# ROM.net
KiCad netlist of a schematic drawn in Altium Designer
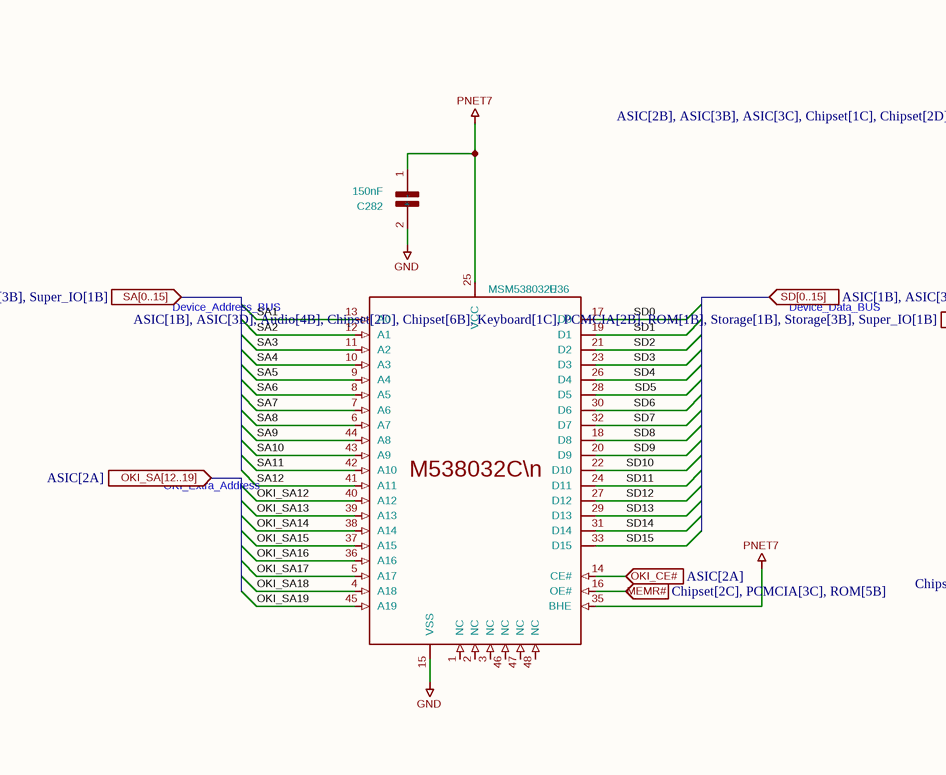
[diagram p0: ROM.SchDoc, left]
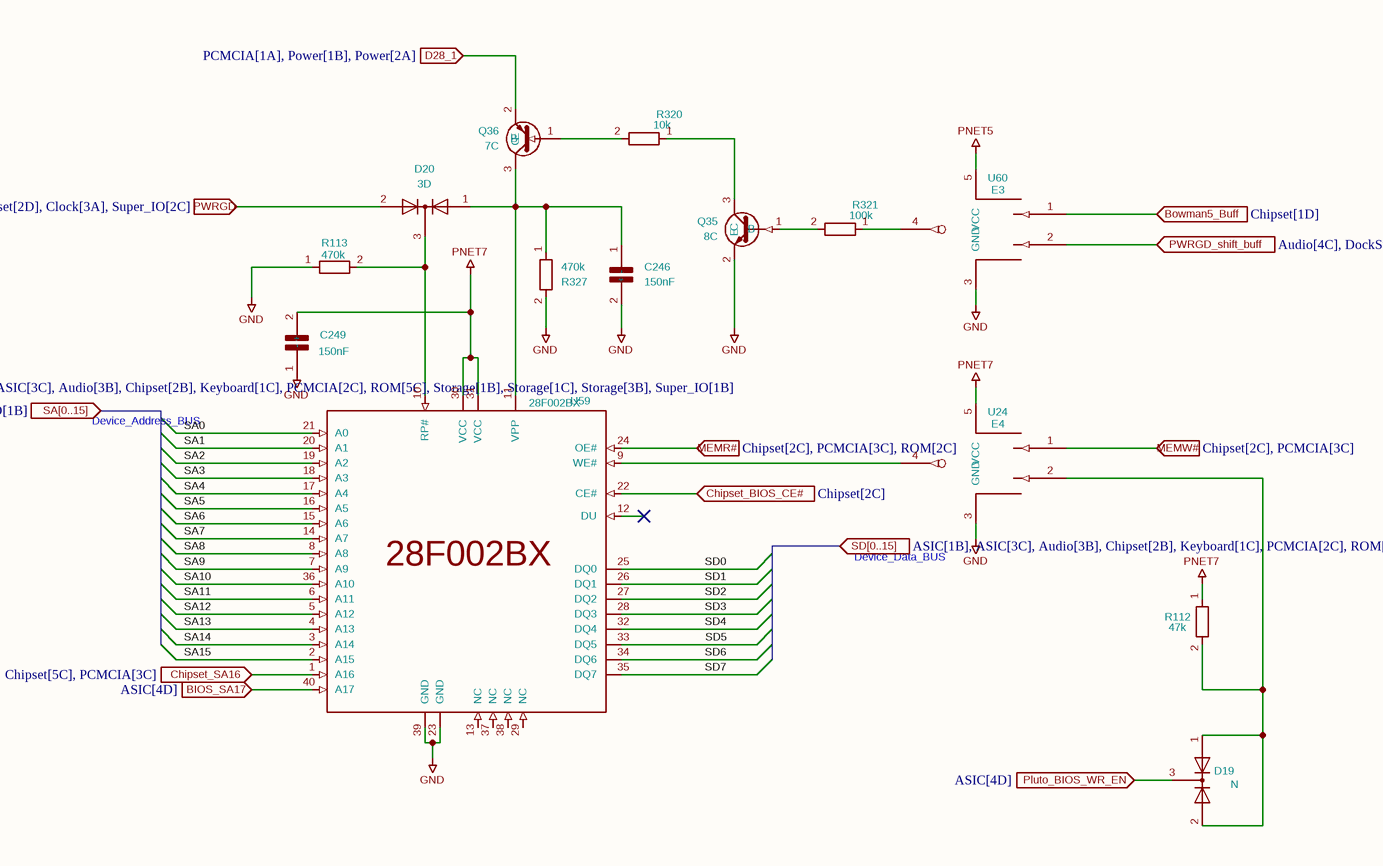
[diagram p1: ROM.SchDoc, right]

(export (version "E")
  (design (tool "Eeschema 10.0.6"))
  (components
    (comp (ref "C246") (value "150nF") (footprint "C_0603_1608Metric") (libsource (lib "") (part "C_1")))
    (comp (ref "C249")
      (value "150nF")
      (footprint "C_0402_1005Metric")
      (libsource (lib "PCM_Elektuur") (part "C"))
    )
    (comp (ref "C282") (value "150nF") (footprint "C_0402_1005Metric") (libsource (lib "") (part "C_1")))
    (comp (ref "D19") (value "N") (footprint "SOT-416L") (libsource (lib "PC110") (part "3D_Diode")))
    (comp (ref "D20") (value "3D") (footprint "SOT-416L") (libsource (lib "PC110") (part "3D_Diode")))
    (comp (ref "Q35") (value "8C") (footprint "SOT-523") (libsource (lib "Transistor_BJT") (part "MMBTA44")))
    (comp (ref "Q36")
      (value "7C")
      (footprint "TSOT-23")
      (libsource (lib "PCM_Transistor_BJT_AKL") (part "Q_PNP_Generic_BEC"))
    )
    (comp (ref "R112") (value "47k") (footprint "R_0402_1005Metric") (libsource (lib "") (part "R_1")))
    (comp (ref "R113") (value "470k") (footprint "R_0402_1005Metric") (libsource (lib "") (part "R_2")))
    (comp (ref "R320") (value "10k") (footprint "R_0402_1005Metric") (libsource (lib "Device") (part "R")))
    (comp (ref "R321") (value "100k") (footprint "R_0402_1005Metric") (libsource (lib "Device") (part "R")))
    (comp (ref "R327") (value "470k") (footprint "R_0402_1005Metric") (libsource (lib "Device") (part "R")))
    (comp (ref "U24") (value "E4") (footprint "SOT-353") (libsource (lib "74xGxx") (part "74AUP1G02")))
    (comp (ref "U36") (value "MSM538032E") (footprint "SOP48") (libsource (lib "PC110") (part "M538032C")))
    (comp (ref "U59") (value "28F002BX") (footprint "Flash-40") (libsource (lib "PC110") (part "28F002BX")))
    (comp (ref "U60") (value "E3") (footprint "SOT-353") (libsource (lib "74xGxx") (part "74AUP1G02")))
  )
  (nets
    (net (code "1") (name "/BIOS_SA17") (class "Default")
      (node (ref "U59") (pin "40") (pinfunction "A17_40") (pintype "input"))
    )
    (net (code "2") (name "/Bowman5_Buff") (class "Default")
      (node (ref "U60") (pin "1") (pinfunction "1_1") (pintype "input"))
    )
    (net (code "3") (name "/Chipset_BIOS_CE#") (class "Default")
      (node (ref "U59") (pin "22") (pinfunction "CE#_22") (pintype "input"))
    )
    (net (code "4") (name "/Chipset_SA16") (class "Default")
      (node (ref "U59") (pin "1") (pinfunction "A16_1") (pintype "input"))
    )
    (net (code "5") (name "/D28_1") (class "Default")
      (node (ref "Q36") (pin "2") (pinfunction "E_2") (pintype "passive"))
    )
    (net (code "6") (name "/MEMR#") (class "Default")
      (node (ref "U36") (pin "16") (pinfunction "OE#_16") (pintype "input"))
      (node (ref "U59") (pin "24") (pinfunction "OE#_24") (pintype "input"))
    )
    (net (code "7") (name "/MEMW#") (class "Default")
      (node (ref "U24") (pin "1") (pinfunction "1_1") (pintype "input"))
    )
    (net (code "8") (name "/OKI_CE#") (class "Default")
      (node (ref "U36") (pin "14") (pinfunction "CE#_14") (pintype "input"))
    )
    (net (code "9") (name "/OKI_SA12") (class "Default")
      (node (ref "U36") (pin "40") (pinfunction "A12_40") (pintype "input"))
    )
    (net (code "10") (name "/OKI_SA13") (class "Default")
      (node (ref "U36") (pin "39") (pinfunction "A13_39") (pintype "input"))
    )
    (net (code "11") (name "/OKI_SA14") (class "Default")
      (node (ref "U36") (pin "38") (pinfunction "A14_38") (pintype "input"))
    )
    (net (code "12") (name "/OKI_SA15") (class "Default")
      (node (ref "U36") (pin "37") (pinfunction "A15_37") (pintype "input"))
    )
    (net (code "13") (name "/OKI_SA16") (class "Default")
      (node (ref "U36") (pin "36") (pinfunction "A16_36") (pintype "input"))
    )
    (net (code "14") (name "/OKI_SA17") (class "Default")
      (node (ref "U36") (pin "5") (pinfunction "A17_5") (pintype "input"))
    )
    (net (code "15") (name "/OKI_SA18") (class "Default")
      (node (ref "U36") (pin "4") (pinfunction "A18_4") (pintype "input"))
    )
    (net (code "16") (name "/OKI_SA19") (class "Default")
      (node (ref "U36") (pin "45") (pinfunction "A19_45") (pintype "input"))
    )
    (net (code "18") (name "/PWRGD") (class "Default")
      (node (ref "D20") (pin "2") (pinfunction "2_2") (pintype "passive"))
    )
    (net (code "19") (name "/PWRGD_shift_buff") (class "Default")
      (node (ref "U60") (pin "2") (pinfunction "2_2") (pintype "input"))
    )
    (net (code "20") (name "/Pluto_BIOS_WR_EN") (class "Default")
      (node (ref "D19") (pin "3") (pinfunction "3_3") (pintype "passive"))
    )
    (net (code "21") (name "/SA0") (class "Default")
      (node (ref "U59") (pin "21") (pinfunction "A0_21") (pintype "input"))
    )
    (net (code "22") (name "/SA1") (class "Default")
      (node (ref "U36") (pin "13") (pinfunction "A0_13") (pintype "input"))
      (node (ref "U59") (pin "20") (pinfunction "A1_20") (pintype "input"))
    )
    (net (code "23") (name "/SA2") (class "Default")
      (node (ref "U36") (pin "12") (pinfunction "A1_12") (pintype "input"))
      (node (ref "U59") (pin "19") (pinfunction "A2_19") (pintype "input"))
    )
    (net (code "24") (name "/SA3") (class "Default")
      (node (ref "U36") (pin "11") (pinfunction "A2_11") (pintype "input"))
      (node (ref "U59") (pin "18") (pinfunction "A3_18") (pintype "input"))
    )
    (net (code "25") (name "/SA4") (class "Default")
      (node (ref "U36") (pin "10") (pinfunction "A3_10") (pintype "input"))
      (node (ref "U59") (pin "17") (pinfunction "A4_17") (pintype "input"))
    )
    (net (code "26") (name "/SA5") (class "Default")
      (node (ref "U36") (pin "9") (pinfunction "A4_9") (pintype "input"))
      (node (ref "U59") (pin "16") (pinfunction "A5_16") (pintype "input"))
    )
    (net (code "27") (name "/SA6") (class "Default")
      (node (ref "U36") (pin "8") (pinfunction "A5_8") (pintype "input"))
      (node (ref "U59") (pin "15") (pinfunction "A6_15") (pintype "input"))
    )
    (net (code "28") (name "/SA7") (class "Default")
      (node (ref "U36") (pin "7") (pinfunction "A6_7") (pintype "input"))
      (node (ref "U59") (pin "14") (pinfunction "A7_14") (pintype "input"))
    )
    (net (code "29") (name "/SA8") (class "Default")
      (node (ref "U36") (pin "6") (pinfunction "A7_6") (pintype "input"))
      (node (ref "U59") (pin "8") (pinfunction "A8_8") (pintype "input"))
    )
    (net (code "30") (name "/SA9") (class "Default")
      (node (ref "U36") (pin "44") (pinfunction "A8_44") (pintype "input"))
      (node (ref "U59") (pin "7") (pinfunction "A9_7") (pintype "input"))
    )
    (net (code "31") (name "/SA10") (class "Default")
      (node (ref "U36") (pin "43") (pinfunction "A9_43") (pintype "input"))
      (node (ref "U59") (pin "36") (pinfunction "A10_36") (pintype "input"))
    )
    (net (code "32") (name "/SA11") (class "Default")
      (node (ref "U36") (pin "42") (pinfunction "A10_42") (pintype "input"))
      (node (ref "U59") (pin "6") (pinfunction "A11_6") (pintype "input"))
    )
    (net (code "33") (name "/SA12") (class "Default")
      (node (ref "U36") (pin "41") (pinfunction "A11_41") (pintype "input"))
      (node (ref "U59") (pin "5") (pinfunction "A12_5") (pintype "input"))
    )
    (net (code "34") (name "/SA13") (class "Default")
      (node (ref "U59") (pin "4") (pinfunction "A13_4") (pintype "input"))
    )
    (net (code "35") (name "/SA14") (class "Default")
      (node (ref "U59") (pin "3") (pinfunction "A14_3") (pintype "input"))
    )
    (net (code "36") (name "/SA15") (class "Default")
      (node (ref "U59") (pin "2") (pinfunction "A15_2") (pintype "input"))
    )
    (net (code "38") (name "/SD0") (class "Default")
      (node (ref "U36") (pin "17") (pinfunction "D0_17") (pintype "bidirectional"))
      (node (ref "U59") (pin "25") (pinfunction "DQ0_25") (pintype "bidirectional"))
    )
    (net (code "39") (name "/SD1") (class "Default")
      (node (ref "U36") (pin "19") (pinfunction "D1_19") (pintype "bidirectional"))
      (node (ref "U59") (pin "26") (pinfunction "DQ1_26") (pintype "bidirectional"))
    )
    (net (code "40") (name "/SD2") (class "Default")
      (node (ref "U36") (pin "21") (pinfunction "D2_21") (pintype "bidirectional"))
      (node (ref "U59") (pin "27") (pinfunction "DQ2_27") (pintype "bidirectional"))
    )
    (net (code "41") (name "/SD3") (class "Default")
      (node (ref "U36") (pin "23") (pinfunction "D3_23") (pintype "bidirectional"))
      (node (ref "U59") (pin "28") (pinfunction "DQ3_28") (pintype "bidirectional"))
    )
    (net (code "42") (name "/SD4") (class "Default")
      (node (ref "U36") (pin "26") (pinfunction "D4_26") (pintype "bidirectional"))
      (node (ref "U59") (pin "32") (pinfunction "DQ4_32") (pintype "bidirectional"))
    )
    (net (code "43") (name "/SD5") (class "Default")
      (node (ref "U36") (pin "28") (pinfunction "D5_28") (pintype "bidirectional"))
      (node (ref "U59") (pin "33") (pinfunction "DQ5_33") (pintype "bidirectional"))
    )
    (net (code "44") (name "/SD6") (class "Default")
      (node (ref "U36") (pin "30") (pinfunction "D6_30") (pintype "bidirectional"))
      (node (ref "U59") (pin "34") (pinfunction "DQ6_34") (pintype "bidirectional"))
    )
    (net (code "45") (name "/SD7") (class "Default")
      (node (ref "U36") (pin "32") (pinfunction "D7_32") (pintype "bidirectional"))
      (node (ref "U59") (pin "35") (pinfunction "DQ7_35") (pintype "bidirectional"))
    )
    (net (code "46") (name "/SD8") (class "Default")
      (node (ref "U36") (pin "18") (pinfunction "D8_18") (pintype "bidirectional"))
    )
    (net (code "47") (name "/SD9") (class "Default")
      (node (ref "U36") (pin "20") (pinfunction "D9_20") (pintype "bidirectional"))
    )
    (net (code "48") (name "/SD10") (class "Default")
      (node (ref "U36") (pin "22") (pinfunction "D10_22") (pintype "bidirectional"))
    )
    (net (code "49") (name "/SD11") (class "Default")
      (node (ref "U36") (pin "24") (pinfunction "D11_24") (pintype "bidirectional"))
    )
    (net (code "50") (name "/SD12") (class "Default")
      (node (ref "U36") (pin "27") (pinfunction "D12_27") (pintype "bidirectional"))
    )
    (net (code "51") (name "/SD13") (class "Default")
      (node (ref "U36") (pin "29") (pinfunction "D13_29") (pintype "bidirectional"))
    )
    (net (code "52") (name "/SD14") (class "Default")
      (node (ref "U36") (pin "31") (pinfunction "D14_31") (pintype "bidirectional"))
    )
    (net (code "53") (name "/SD15") (class "Default")
      (node (ref "U36") (pin "33") (pinfunction "D15_33") (pintype "bidirectional"))
    )
    (net (code "55") (name "GND") (class "Default")
      (node (ref "C246") (pin "2") (pinfunction "-_2") (pintype "passive"))
      (node (ref "C249") (pin "1") (pinfunction "+_1") (pintype "passive"))
      (node (ref "C282") (pin "2") (pinfunction "-_2") (pintype "passive"))
      (node (ref "Q35") (pin "2") (pinfunction "E_2") (pintype "passive"))
      (node (ref "R113") (pin "1") (pinfunction "1_1") (pintype "passive"))
      (node (ref "R327") (pin "2") (pinfunction "2_2") (pintype "passive"))
      (node (ref "U24") (pin "3") (pinfunction "GND_3") (pintype "power_in"))
      (node (ref "U36") (pin "15") (pinfunction "VSS_15") (pintype "power_in"))
      (node (ref "U59") (pin "23") (pinfunction "GND_23") (pintype "power_in"))
      (node (ref "U59") (pin "39") (pinfunction "GND_39") (pintype "power_in"))
      (node (ref "U60") (pin "3") (pinfunction "GND_3") (pintype "power_in"))
    )
    (net (code "56") (name "Net-(C246-+)") (class "Default")
      (node (ref "C246") (pin "1") (pinfunction "+_1") (pintype "passive"))
      (node (ref "D20") (pin "1") (pinfunction "1_1") (pintype "passive"))
      (node (ref "Q36") (pin "3") (pinfunction "C_3") (pintype "passive"))
      (node (ref "R327") (pin "1") (pinfunction "1_1") (pintype "passive"))
      (node (ref "U59") (pin "11") (pinfunction "VPP_11") (pintype "power_in"))
    )
    (net (code "57") (name "Net-(D19-Pad1)") (class "Default")
      (node (ref "D19") (pin "1") (pinfunction "1_1") (pintype "passive"))
      (node (ref "D19") (pin "2") (pinfunction "2_2") (pintype "passive"))
      (node (ref "R112") (pin "2") (pinfunction "2_2") (pintype "passive"))
      (node (ref "U24") (pin "2") (pinfunction "2_2") (pintype "input"))
    )
    (net (code "58") (name "Net-(Q35-B)") (class "Default")
      (node (ref "Q35") (pin "1") (pinfunction "B_1") (pintype "input"))
      (node (ref "R321") (pin "2") (pinfunction "2_2") (pintype "passive"))
    )
    (net (code "59") (name "Net-(Q35-C)") (class "Default")
      (node (ref "Q35") (pin "3") (pinfunction "C_3") (pintype "passive"))
      (node (ref "R320") (pin "1") (pinfunction "1_1") (pintype "passive"))
    )
    (net (code "60") (name "Net-(Q36-B)") (class "Default")
      (node (ref "Q36") (pin "1") (pinfunction "B_1") (pintype "input"))
      (node (ref "R320") (pin "2") (pinfunction "2_2") (pintype "passive"))
    )
    (net (code "61") (name "Net-(R321-Pad1)") (class "Default")
      (node (ref "R321") (pin "1") (pinfunction "1_1") (pintype "passive"))
      (node (ref "U60") (pin "4") (pinfunction "4_4") (pintype "output"))
    )
    (net (code "62") (name "Net-(U59-RP#)") (class "Default")
      (node (ref "D20") (pin "3") (pinfunction "3_3") (pintype "passive"))
      (node (ref "R113") (pin "2") (pinfunction "2_2") (pintype "passive"))
      (node (ref "U59") (pin "10") (pinfunction "RP#_10") (pintype "input"))
    )
    (net (code "63") (name "Net-(U59-WE#)") (class "Default")
      (node (ref "U24") (pin "4") (pinfunction "4_4") (pintype "output"))
      (node (ref "U59") (pin "9") (pinfunction "WE#_9") (pintype "input"))
    )
    (net (code "64") (name "PNET5") (class "Default")
      (node (ref "U60") (pin "5") (pinfunction "VCC_5") (pintype "power_in"))
    )
    (net (code "65") (name "PNET7") (class "Default")
      (node (ref "C249") (pin "2") (pinfunction "-_2") (pintype "passive"))
      (node (ref "C282") (pin "1") (pinfunction "+_1") (pintype "passive"))
      (node (ref "R112") (pin "1") (pinfunction "1_1") (pintype "passive"))
      (node (ref "U24") (pin "5") (pinfunction "VCC_5") (pintype "power_in"))
      (node (ref "U36") (pin "25") (pinfunction "VCC_25") (pintype "power_in"))
      (node (ref "U36") (pin "35") (pinfunction "BHE_35") (pintype "input"))
      (node (ref "U59") (pin "30") (pinfunction "VCC_30") (pintype "power_in"))
      (node (ref "U59") (pin "31") (pinfunction "VCC_31") (pintype "power_in"))
    )
    (net (code "66") (name "unconnected-(U36-NC-Pad1)") (class "Default")
      (node (ref "U36") (pin "1") (pinfunction "NC_1") (pintype "input"))
    )
    (net (code "67") (name "unconnected-(U36-NC-Pad2)") (class "Default")
      (node (ref "U36") (pin "2") (pinfunction "NC_2") (pintype "input"))
    )
    (net (code "68") (name "unconnected-(U36-NC-Pad3)") (class "Default")
      (node (ref "U36") (pin "3") (pinfunction "NC_3") (pintype "input"))
    )
    (net (code "69") (name "unconnected-(U36-NC-Pad46)") (class "Default")
      (node (ref "U36") (pin "46") (pinfunction "NC_46") (pintype "input"))
    )
    (net (code "70") (name "unconnected-(U36-NC-Pad47)") (class "Default")
      (node (ref "U36") (pin "47") (pinfunction "NC_47") (pintype "input"))
    )
    (net (code "71") (name "unconnected-(U36-NC-Pad48)") (class "Default")
      (node (ref "U36") (pin "48") (pinfunction "NC_48") (pintype "input"))
    )
    (net (code "72") (name "unconnected-(U59-DU-Pad12)") (class "Default")
      (node (ref "U59") (pin "12") (pinfunction "DU_12") (pintype "input+no_connect"))
    )
    (net (code "73") (name "unconnected-(U59-NC-Pad13)") (class "Default")
      (node (ref "U59") (pin "13") (pinfunction "NC_13") (pintype "input"))
    )
    (net (code "74") (name "unconnected-(U59-NC-Pad29)") (class "Default")
      (node (ref "U59") (pin "29") (pinfunction "NC_29") (pintype "input"))
    )
    (net (code "75") (name "unconnected-(U59-NC-Pad37)") (class "Default")
      (node (ref "U59") (pin "37") (pinfunction "NC_37") (pintype "input"))
    )
    (net (code "76") (name "unconnected-(U59-NC-Pad38)") (class "Default")
      (node (ref "U59") (pin "38") (pinfunction "NC_38") (pintype "input"))
    )
  )
)
